# 6button-6neopixel.net
KiCad netlist of a schematic drawn in Altium Designer
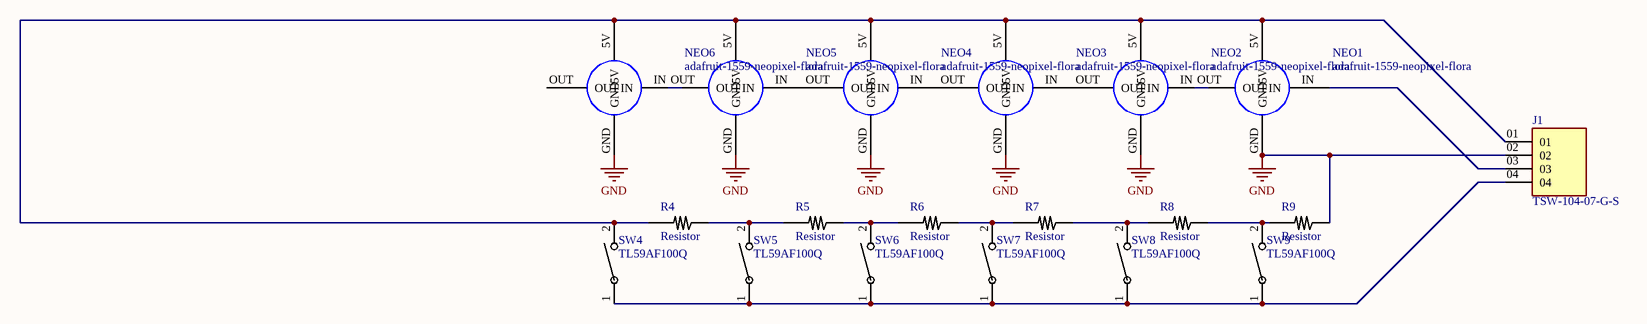
[diagram p0: 6button-6neopixel.SchDoc]

(export (version "E")
  (design (tool "Eeschema 10.0.6"))
  (components
    (comp (ref "J1")
      (value "TSW-104-07-G-S")
      (footprint "SAMTEC_TSW-104-07-G-S")
      (fields (field (name "MP") "altium_native_batch"))
      (libsource (lib "SchlibLafe") (part "TSW-104-07-G-S"))
    )
    (comp (ref "NEO1")
      (value "adafruit-1559-neopixel-flora")
      (footprint "adafruit-1559-neopixel-flora")
      (libsource (lib "SchlibLafe") (part "adafruit-1559-neopixel-flora"))
    )
    (comp (ref "NEO2")
      (value "adafruit-1559-neopixel-flora")
      (footprint "adafruit-1559-neopixel-flora")
      (libsource (lib "SchlibLafe") (part "adafruit-1559-neopixel-flora"))
    )
    (comp (ref "NEO3")
      (value "adafruit-1559-neopixel-flora")
      (footprint "adafruit-1559-neopixel-flora")
      (libsource (lib "SchlibLafe") (part "adafruit-1559-neopixel-flora"))
    )
    (comp (ref "NEO4")
      (value "adafruit-1559-neopixel-flora")
      (footprint "adafruit-1559-neopixel-flora")
      (libsource (lib "SchlibLafe") (part "adafruit-1559-neopixel-flora"))
    )
    (comp (ref "NEO5")
      (value "adafruit-1559-neopixel-flora")
      (footprint "adafruit-1559-neopixel-flora")
      (libsource (lib "SchlibLafe") (part "adafruit-1559-neopixel-flora"))
    )
    (comp (ref "NEO6")
      (value "adafruit-1559-neopixel-flora")
      (footprint "adafruit-1559-neopixel-flora")
      (libsource (lib "SchlibLafe") (part "adafruit-1559-neopixel-flora"))
    )
    (comp (ref "R4")
      (value "Resistor")
      (footprint "thruhole resistor")
      (libsource (lib "SchlibLafe") (part "Resistor"))
    )
    (comp (ref "R5")
      (value "Resistor")
      (footprint "thruhole resistor")
      (libsource (lib "SchlibLafe") (part "Resistor"))
    )
    (comp (ref "R6")
      (value "Resistor")
      (footprint "thruhole resistor")
      (libsource (lib "SchlibLafe") (part "Resistor"))
    )
    (comp (ref "R7")
      (value "Resistor")
      (footprint "thruhole resistor")
      (libsource (lib "SchlibLafe") (part "Resistor"))
    )
    (comp (ref "R8")
      (value "Resistor")
      (footprint "thruhole resistor")
      (libsource (lib "SchlibLafe") (part "Resistor"))
    )
    (comp (ref "R9")
      (value "Resistor")
      (footprint "thruhole resistor")
      (libsource (lib "SchlibLafe") (part "Resistor"))
    )
    (comp (ref "SW4")
      (value "TL59AF100Q")
      (footprint "SW_TL59AF100Q_EWI")
      (description "No Description Available")
      (fields (field (name "COPYRIGHT") "Copyright (C) 2024 Ultra Librarian. All rights reserved."))
      (libsource (lib "SchlibLafe") (part "TL59AF100Q"))
    )
    (comp (ref "SW5")
      (value "TL59AF100Q")
      (footprint "SW_TL59AF100Q_EWI")
      (description "No Description Available")
      (fields (field (name "COPYRIGHT") "Copyright (C) 2024 Ultra Librarian. All rights reserved."))
      (libsource (lib "SchlibLafe") (part "TL59AF100Q"))
    )
    (comp (ref "SW6")
      (value "TL59AF100Q")
      (footprint "SW_TL59AF100Q_EWI")
      (description "No Description Available")
      (fields (field (name "COPYRIGHT") "Copyright (C) 2024 Ultra Librarian. All rights reserved."))
      (libsource (lib "SchlibLafe") (part "TL59AF100Q"))
    )
    (comp (ref "SW7")
      (value "TL59AF100Q")
      (footprint "SW_TL59AF100Q_EWI")
      (description "No Description Available")
      (fields (field (name "COPYRIGHT") "Copyright (C) 2024 Ultra Librarian. All rights reserved."))
      (libsource (lib "SchlibLafe") (part "TL59AF100Q"))
    )
    (comp (ref "SW8")
      (value "TL59AF100Q")
      (footprint "SW_TL59AF100Q_EWI")
      (description "No Description Available")
      (fields (field (name "COPYRIGHT") "Copyright (C) 2024 Ultra Librarian. All rights reserved."))
      (libsource (lib "SchlibLafe") (part "TL59AF100Q"))
    )
    (comp (ref "SW9")
      (value "TL59AF100Q")
      (footprint "SW_TL59AF100Q_EWI")
      (description "No Description Available")
      (fields (field (name "COPYRIGHT") "Copyright (C) 2024 Ultra Librarian. All rights reserved."))
      (libsource (lib "SchlibLafe") (part "TL59AF100Q"))
    )
  )
  (nets
    (net (code "1") (name "GND") (class "Default")
      (node (ref "J1") (pin "02") (pinfunction "02_02") (pintype "passive"))
      (node (ref "NEO1") (pin "GND") (pinfunction "GND_GND") (pintype "passive"))
      (node (ref "NEO2") (pin "GND") (pinfunction "GND_GND") (pintype "passive"))
      (node (ref "NEO3") (pin "GND") (pinfunction "GND_GND") (pintype "passive"))
      (node (ref "NEO4") (pin "GND") (pinfunction "GND_GND") (pintype "passive"))
      (node (ref "NEO5") (pin "GND") (pinfunction "GND_GND") (pintype "passive"))
      (node (ref "NEO6") (pin "GND") (pinfunction "GND_GND") (pintype "passive"))
      (node (ref "R9") (pin "1") (pinfunction "1_1") (pintype "passive"))
    )
    (net (code "2") (name "Net-(J1-Pad01)") (class "Default")
      (node (ref "J1") (pin "01") (pinfunction "01_01") (pintype "passive"))
      (node (ref "NEO1") (pin "5V") (pinfunction "5V_5V") (pintype "passive"))
      (node (ref "NEO2") (pin "5V") (pinfunction "5V_5V") (pintype "passive"))
      (node (ref "NEO3") (pin "5V") (pinfunction "5V_5V") (pintype "passive"))
      (node (ref "NEO4") (pin "5V") (pinfunction "5V_5V") (pintype "passive"))
      (node (ref "NEO5") (pin "5V") (pinfunction "5V_5V") (pintype "passive"))
      (node (ref "NEO6") (pin "5V") (pinfunction "5V_5V") (pintype "passive"))
      (node (ref "R4") (pin "2") (pinfunction "2_2") (pintype "passive"))
      (node (ref "SW4") (pin "2") (pinfunction "2_2") (pintype "passive"))
    )
    (net (code "3") (name "Net-(J1-Pad03)") (class "Default")
      (node (ref "J1") (pin "03") (pinfunction "03_03") (pintype "passive"))
      (node (ref "NEO1") (pin "IN") (pinfunction "IN_IN") (pintype "passive"))
    )
    (net (code "4") (name "Net-(J1-Pad04)") (class "Default")
      (node (ref "J1") (pin "04") (pinfunction "04_04") (pintype "passive"))
      (node (ref "SW4") (pin "1") (pinfunction "1_1") (pintype "passive"))
      (node (ref "SW5") (pin "1") (pinfunction "1_1") (pintype "passive"))
      (node (ref "SW6") (pin "1") (pinfunction "1_1") (pintype "passive"))
      (node (ref "SW7") (pin "1") (pinfunction "1_1") (pintype "passive"))
      (node (ref "SW8") (pin "1") (pinfunction "1_1") (pintype "passive"))
      (node (ref "SW9") (pin "1") (pinfunction "1_1") (pintype "passive"))
    )
    (net (code "5") (name "Net-(NEO1-PadOUT)") (class "Default")
      (node (ref "NEO1") (pin "OUT") (pinfunction "OUT_OUT") (pintype "passive"))
      (node (ref "NEO2") (pin "IN") (pinfunction "IN_IN") (pintype "passive"))
    )
    (net (code "6") (name "Net-(NEO2-PadOUT)") (class "Default")
      (node (ref "NEO2") (pin "OUT") (pinfunction "OUT_OUT") (pintype "passive"))
      (node (ref "NEO3") (pin "IN") (pinfunction "IN_IN") (pintype "passive"))
    )
    (net (code "7") (name "Net-(NEO3-PadOUT)") (class "Default")
      (node (ref "NEO3") (pin "OUT") (pinfunction "OUT_OUT") (pintype "passive"))
      (node (ref "NEO4") (pin "IN") (pinfunction "IN_IN") (pintype "passive"))
    )
    (net (code "8") (name "Net-(NEO4-PadOUT)") (class "Default")
      (node (ref "NEO4") (pin "OUT") (pinfunction "OUT_OUT") (pintype "passive"))
      (node (ref "NEO5") (pin "IN") (pinfunction "IN_IN") (pintype "passive"))
    )
    (net (code "9") (name "Net-(NEO5-PadOUT)") (class "Default")
      (node (ref "NEO5") (pin "OUT") (pinfunction "OUT_OUT") (pintype "passive"))
      (node (ref "NEO6") (pin "IN") (pinfunction "IN_IN") (pintype "passive"))
    )
    (net (code "10") (name "Net-(R4-Pad1)") (class "Default")
      (node (ref "R4") (pin "1") (pinfunction "1_1") (pintype "passive"))
      (node (ref "R5") (pin "2") (pinfunction "2_2") (pintype "passive"))
      (node (ref "SW5") (pin "2") (pinfunction "2_2") (pintype "passive"))
    )
    (net (code "11") (name "Net-(R5-Pad1)") (class "Default")
      (node (ref "R5") (pin "1") (pinfunction "1_1") (pintype "passive"))
      (node (ref "R6") (pin "2") (pinfunction "2_2") (pintype "passive"))
      (node (ref "SW6") (pin "2") (pinfunction "2_2") (pintype "passive"))
    )
    (net (code "12") (name "Net-(R6-Pad1)") (class "Default")
      (node (ref "R6") (pin "1") (pinfunction "1_1") (pintype "passive"))
      (node (ref "R7") (pin "2") (pinfunction "2_2") (pintype "passive"))
      (node (ref "SW7") (pin "2") (pinfunction "2_2") (pintype "passive"))
    )
    (net (code "13") (name "Net-(R7-Pad1)") (class "Default")
      (node (ref "R7") (pin "1") (pinfunction "1_1") (pintype "passive"))
      (node (ref "R8") (pin "2") (pinfunction "2_2") (pintype "passive"))
      (node (ref "SW8") (pin "2") (pinfunction "2_2") (pintype "passive"))
    )
    (net (code "14") (name "Net-(R8-Pad1)") (class "Default")
      (node (ref "R8") (pin "1") (pinfunction "1_1") (pintype "passive"))
      (node (ref "R9") (pin "2") (pinfunction "2_2") (pintype "passive"))
      (node (ref "SW9") (pin "2") (pinfunction "2_2") (pintype "passive"))
    )
    (net (code "15") (name "unconnected-(NEO6-PadOUT)") (class "Default")
      (node (ref "NEO6") (pin "OUT") (pinfunction "OUT_OUT") (pintype "passive"))
    )
  )
)
